# Hatch2021Badge0805_1.net
KiCad netlist of a schematic drawn in EAGLE
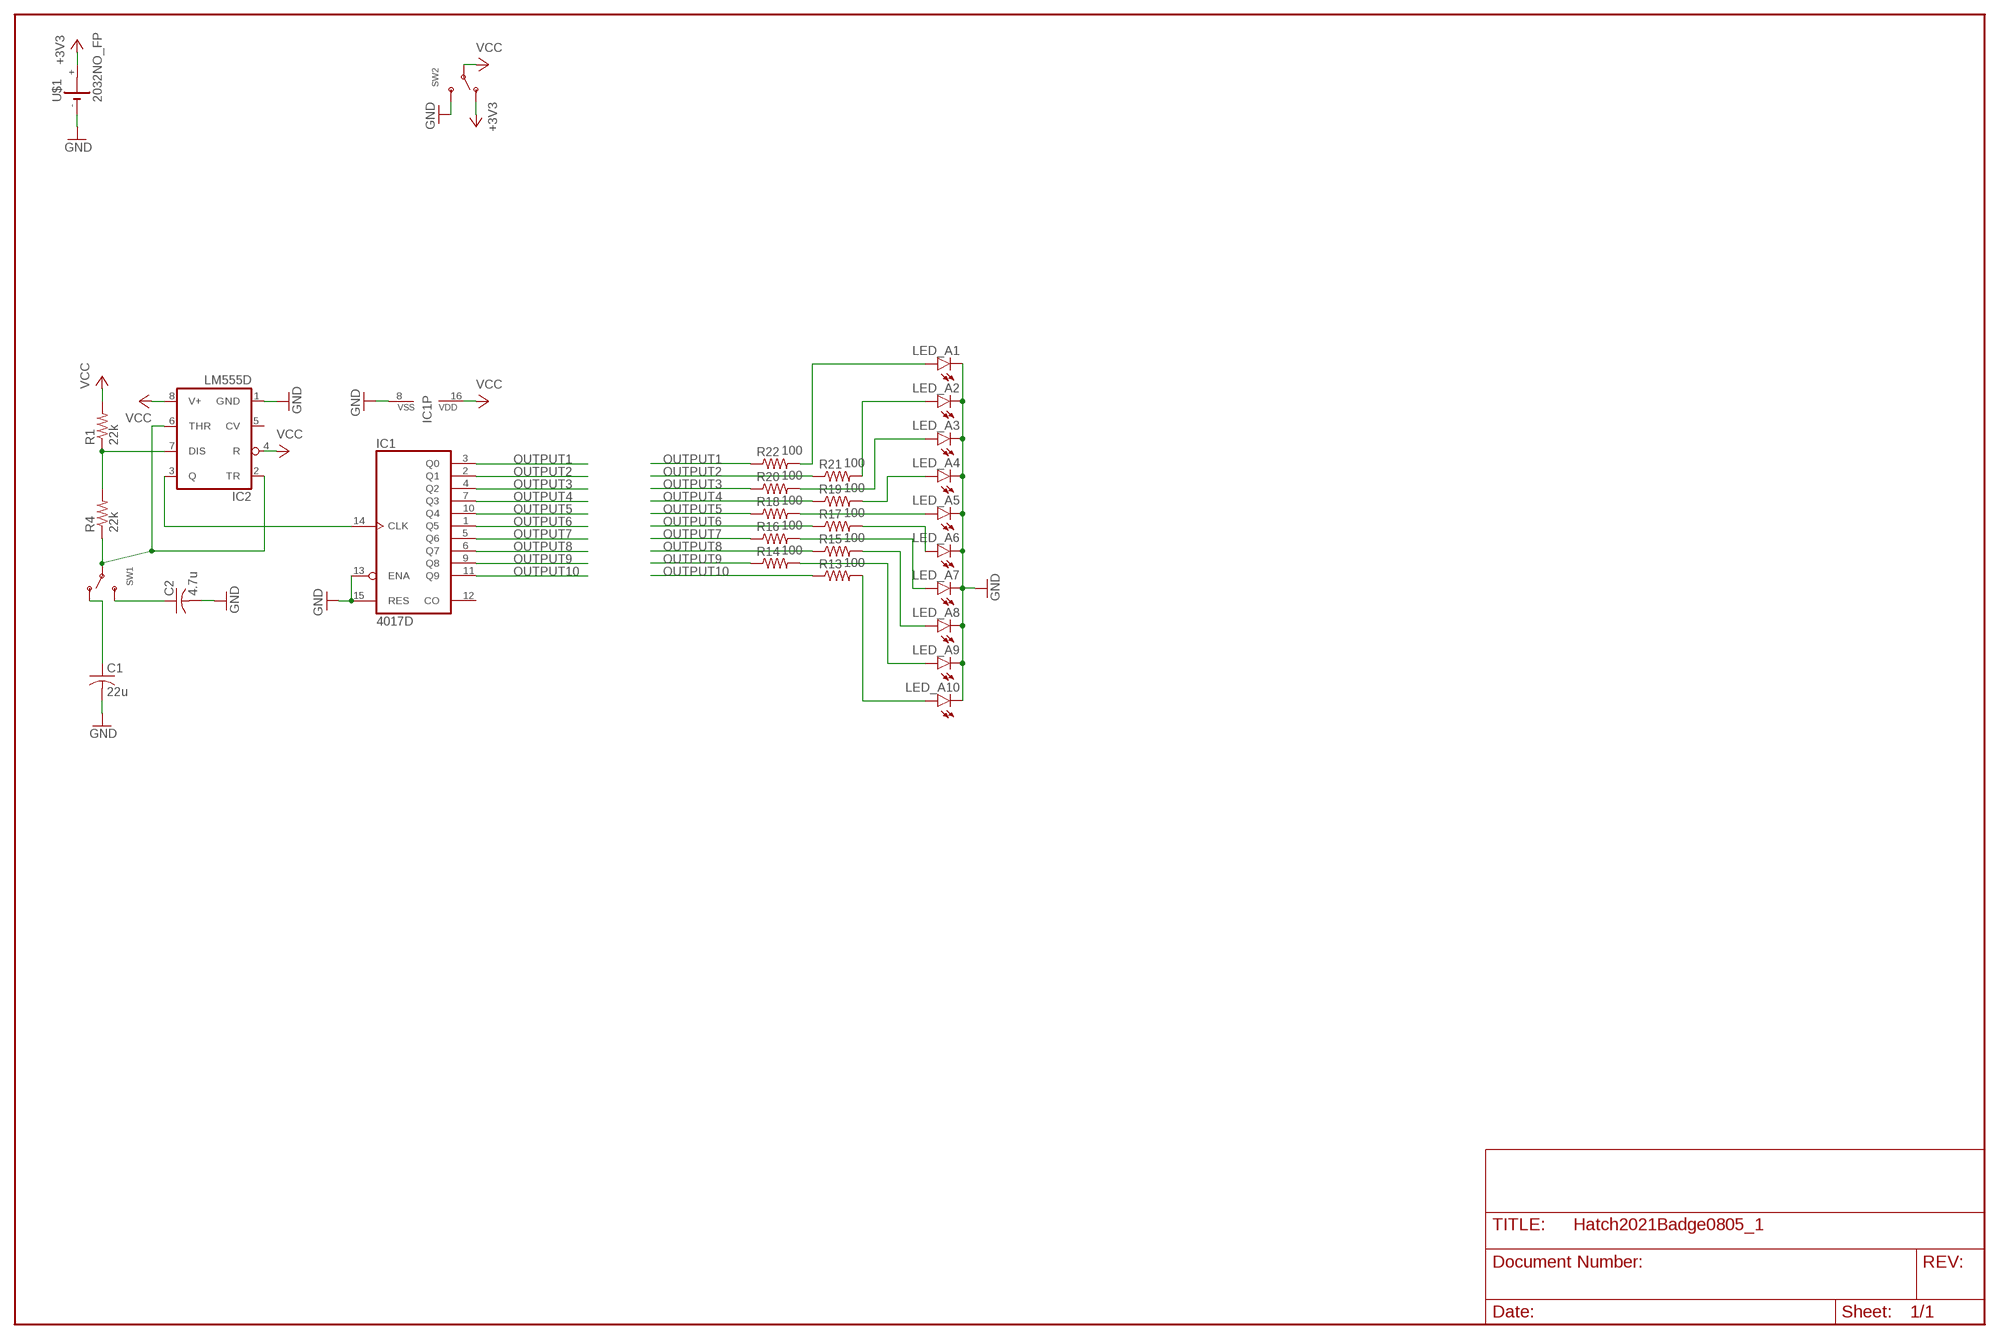
[diagram p0: schematic, sheet 1]

(export (version "E")
  (design (tool "Eeschema 10.0.6"))
  (components
    (comp (ref "C1")
      (value "22u")
      (footprint "eagle-import:C0805")
      (libsource (lib "eagle-import") (part "C-USC0805"))
    )
    (comp (ref "C2")
      (value "4.7u")
      (footprint "eagle-import:C0805")
      (libsource (lib "eagle-import") (part "C-USC0805"))
    )
    (comp (ref "IC1")
      (value "4017D")
      (footprint "eagle-import:SO16")
      (libsource (lib "eagle-import") (part "4017D"))
    )
    (comp (ref "IC2")
      (value "LM555D")
      (footprint "eagle-import:SO08")
      (libsource (lib "eagle-import") (part "555DLM"))
    )
    (comp (ref "LED_A1")
      (value "LEDSML0805")
      (footprint "eagle-import:SML0805")
      (libsource (lib "eagle-import") (part "LEDSML0805"))
    )
    (comp (ref "LED_A2")
      (value "LEDSML0805")
      (footprint "eagle-import:SML0805")
      (libsource (lib "eagle-import") (part "LEDSML0805"))
    )
    (comp (ref "LED_A3")
      (value "LEDSML0805")
      (footprint "eagle-import:SML0805")
      (libsource (lib "eagle-import") (part "LEDSML0805"))
    )
    (comp (ref "LED_A4")
      (value "LEDSML0805")
      (footprint "eagle-import:SML0805")
      (libsource (lib "eagle-import") (part "LEDSML0805"))
    )
    (comp (ref "LED_A5")
      (value "LEDSML0805")
      (footprint "eagle-import:SML0805")
      (libsource (lib "eagle-import") (part "LEDSML0805"))
    )
    (comp (ref "LED_A6")
      (value "LEDSML0805")
      (footprint "eagle-import:SML0805")
      (libsource (lib "eagle-import") (part "LEDSML0805"))
    )
    (comp (ref "LED_A7")
      (value "LEDSML0805")
      (footprint "eagle-import:SML0805")
      (libsource (lib "eagle-import") (part "LEDSML0805"))
    )
    (comp (ref "LED_A8")
      (value "LEDSML0805")
      (footprint "eagle-import:SML0805")
      (libsource (lib "eagle-import") (part "LEDSML0805"))
    )
    (comp (ref "LED_A9")
      (value "LEDSML0805")
      (footprint "eagle-import:SML0805")
      (libsource (lib "eagle-import") (part "LEDSML0805"))
    )
    (comp (ref "LED_A10")
      (value "LEDSML0805")
      (footprint "eagle-import:SML0805")
      (libsource (lib "eagle-import") (part "LEDSML0805"))
    )
    (comp (ref "R1")
      (value "22k")
      (footprint "eagle-import:R0805")
      (libsource (lib "eagle-import") (part "R-US_R0805"))
    )
    (comp (ref "R4")
      (value "22k")
      (footprint "eagle-import:R0805")
      (libsource (lib "eagle-import") (part "R-US_R0805"))
    )
    (comp (ref "R13")
      (value "100")
      (footprint "eagle-import:R0805")
      (libsource (lib "eagle-import") (part "R-US_R0805"))
    )
    (comp (ref "R14")
      (value "100")
      (footprint "eagle-import:R0805")
      (libsource (lib "eagle-import") (part "R-US_R0805"))
    )
    (comp (ref "R15")
      (value "100")
      (footprint "eagle-import:R0805")
      (libsource (lib "eagle-import") (part "R-US_R0805"))
    )
    (comp (ref "R16")
      (value "100")
      (footprint "eagle-import:R0805")
      (libsource (lib "eagle-import") (part "R-US_R0805"))
    )
    (comp (ref "R17")
      (value "100")
      (footprint "eagle-import:R0805")
      (libsource (lib "eagle-import") (part "R-US_R0805"))
    )
    (comp (ref "R18")
      (value "100")
      (footprint "eagle-import:R0805")
      (libsource (lib "eagle-import") (part "R-US_R0805"))
    )
    (comp (ref "R19")
      (value "100")
      (footprint "eagle-import:R0805")
      (libsource (lib "eagle-import") (part "R-US_R0805"))
    )
    (comp (ref "R20")
      (value "100")
      (footprint "eagle-import:R0805")
      (libsource (lib "eagle-import") (part "R-US_R0805"))
    )
    (comp (ref "R21")
      (value "100")
      (footprint "eagle-import:R0805")
      (libsource (lib "eagle-import") (part "R-US_R0805"))
    )
    (comp (ref "R22")
      (value "100")
      (footprint "eagle-import:R0805")
      (libsource (lib "eagle-import") (part "R-US_R0805"))
    )
    (comp (ref "SW1")
      (value "SWITCH_SPDT")
      (footprint "eagle-import:SPDT_SMT_SSSS811101")
      (libsource (lib "eagle-import") (part "SWITCH_SPDT"))
    )
    (comp (ref "SW2")
      (value "SWITCH_SPDT")
      (footprint "eagle-import:SPDT_SMT_SSSS811101")
      (libsource (lib "eagle-import") (part "SWITCH_SPDT"))
    )
    (comp (ref "U$1")
      (value "2032NO_FP")
      (footprint "eagle-import:2032_NO_FP")
      (libsource (lib "eagle-import") (part "2032NO_FP"))
    )
  )
  (nets
    (net (code "1") (name "+3V3") (class "Default")
      (node (ref "SW2") (pin "A") (pinfunction "O_A") (pintype "passive"))
      (node (ref "U$1") (pin "+") (pinfunction "+_+") (pintype "passive"))
    )
    (net (code "2") (name "/OUTPUT1") (class "Default")
      (node (ref "IC1") (pin "3") (pinfunction "Q0_3") (pintype "output"))
      (node (ref "R22") (pin "1") (pinfunction "1_1") (pintype "passive"))
    )
    (net (code "3") (name "/OUTPUT2") (class "Default")
      (node (ref "IC1") (pin "2") (pinfunction "Q1_2") (pintype "output"))
      (node (ref "R21") (pin "1") (pinfunction "1_1") (pintype "passive"))
    )
    (net (code "4") (name "/OUTPUT3") (class "Default")
      (node (ref "IC1") (pin "4") (pinfunction "Q2_4") (pintype "output"))
      (node (ref "R20") (pin "1") (pinfunction "1_1") (pintype "passive"))
    )
    (net (code "5") (name "/OUTPUT4") (class "Default")
      (node (ref "IC1") (pin "7") (pinfunction "Q3_7") (pintype "output"))
      (node (ref "R19") (pin "1") (pinfunction "1_1") (pintype "passive"))
    )
    (net (code "6") (name "/OUTPUT5") (class "Default")
      (node (ref "IC1") (pin "10") (pinfunction "Q4_10") (pintype "output"))
      (node (ref "R18") (pin "1") (pinfunction "1_1") (pintype "passive"))
    )
    (net (code "7") (name "/OUTPUT6") (class "Default")
      (node (ref "IC1") (pin "1") (pinfunction "Q5_1") (pintype "output"))
      (node (ref "R17") (pin "1") (pinfunction "1_1") (pintype "passive"))
    )
    (net (code "8") (name "/OUTPUT7") (class "Default")
      (node (ref "IC1") (pin "5") (pinfunction "Q6_5") (pintype "output"))
      (node (ref "R16") (pin "1") (pinfunction "1_1") (pintype "passive"))
    )
    (net (code "9") (name "/OUTPUT8") (class "Default")
      (node (ref "IC1") (pin "6") (pinfunction "Q7_6") (pintype "output"))
      (node (ref "R15") (pin "1") (pinfunction "1_1") (pintype "passive"))
    )
    (net (code "10") (name "/OUTPUT9") (class "Default")
      (node (ref "IC1") (pin "9") (pinfunction "Q8_9") (pintype "output"))
      (node (ref "R14") (pin "1") (pinfunction "1_1") (pintype "passive"))
    )
    (net (code "11") (name "/OUTPUT10") (class "Default")
      (node (ref "IC1") (pin "11") (pinfunction "Q9_11") (pintype "output"))
      (node (ref "R13") (pin "1") (pinfunction "1_1") (pintype "passive"))
    )
    (net (code "12") (name "GND") (class "Default")
      (node (ref "C1") (pin "2") (pinfunction "2_2") (pintype "passive"))
      (node (ref "C2") (pin "2") (pinfunction "2_2") (pintype "passive"))
      (node (ref "IC1") (pin "13") (pinfunction "ENA_13") (pintype "input"))
      (node (ref "IC1") (pin "15") (pinfunction "RES_15") (pintype "input"))
      (node (ref "IC1") (pin "8") (pinfunction "VSS_8") (pintype "power_in"))
      (node (ref "IC2") (pin "1") (pinfunction "GND_1") (pintype "power_in"))
      (node (ref "LED_A1") (pin "C") (pinfunction "C_C") (pintype "passive"))
      (node (ref "LED_A10") (pin "C") (pinfunction "C_C") (pintype "passive"))
      (node (ref "LED_A2") (pin "C") (pinfunction "C_C") (pintype "passive"))
      (node (ref "LED_A3") (pin "C") (pinfunction "C_C") (pintype "passive"))
      (node (ref "LED_A4") (pin "C") (pinfunction "C_C") (pintype "passive"))
      (node (ref "LED_A5") (pin "C") (pinfunction "C_C") (pintype "passive"))
      (node (ref "LED_A6") (pin "C") (pinfunction "C_C") (pintype "passive"))
      (node (ref "LED_A7") (pin "C") (pinfunction "C_C") (pintype "passive"))
      (node (ref "LED_A8") (pin "C") (pinfunction "C_C") (pintype "passive"))
      (node (ref "LED_A9") (pin "C") (pinfunction "C_C") (pintype "passive"))
      (node (ref "SW2") (pin "C") (pinfunction "S_C") (pintype "passive"))
      (node (ref "U$1") (pin "-") (pinfunction "-_-") (pintype "passive"))
    )
    (net (code "13") (name "Net-(IC1A-CLK)") (class "Default")
      (node (ref "IC1") (pin "14") (pinfunction "CLK_14") (pintype "input"))
      (node (ref "IC2") (pin "3") (pinfunction "Q_3") (pintype "output"))
    )
    (net (code "14") (name "Net-(IC2-DIS)") (class "Default")
      (node (ref "IC2") (pin "7") (pinfunction "DIS_7") (pintype "input"))
      (node (ref "R1") (pin "1") (pinfunction "1_1") (pintype "passive"))
      (node (ref "R4") (pin "2") (pinfunction "2_2") (pintype "passive"))
    )
    (net (code "15") (name "Net-(IC2-THR)") (class "Default")
      (node (ref "IC2") (pin "2") (pinfunction "TR_2") (pintype "input"))
      (node (ref "IC2") (pin "6") (pinfunction "THR_6") (pintype "input"))
      (node (ref "R4") (pin "1") (pinfunction "1_1") (pintype "passive"))
      (node (ref "SW1") (pin "B") (pinfunction "P_B") (pintype "passive"))
    )
    (net (code "16") (name "Net-(LED_A1-PadA)") (class "Default")
      (node (ref "LED_A1") (pin "A") (pinfunction "A_A") (pintype "passive"))
      (node (ref "R22") (pin "2") (pinfunction "2_2") (pintype "passive"))
    )
    (net (code "17") (name "Net-(LED_A2-PadA)") (class "Default")
      (node (ref "LED_A2") (pin "A") (pinfunction "A_A") (pintype "passive"))
      (node (ref "R21") (pin "2") (pinfunction "2_2") (pintype "passive"))
    )
    (net (code "18") (name "Net-(LED_A3-PadA)") (class "Default")
      (node (ref "LED_A3") (pin "A") (pinfunction "A_A") (pintype "passive"))
      (node (ref "R20") (pin "2") (pinfunction "2_2") (pintype "passive"))
    )
    (net (code "19") (name "Net-(LED_A4-PadA)") (class "Default")
      (node (ref "LED_A4") (pin "A") (pinfunction "A_A") (pintype "passive"))
      (node (ref "R19") (pin "2") (pinfunction "2_2") (pintype "passive"))
    )
    (net (code "20") (name "Net-(LED_A5-PadA)") (class "Default")
      (node (ref "LED_A5") (pin "A") (pinfunction "A_A") (pintype "passive"))
      (node (ref "R18") (pin "2") (pinfunction "2_2") (pintype "passive"))
    )
    (net (code "21") (name "Net-(LED_A6-PadA)") (class "Default")
      (node (ref "LED_A6") (pin "A") (pinfunction "A_A") (pintype "passive"))
      (node (ref "R17") (pin "2") (pinfunction "2_2") (pintype "passive"))
    )
    (net (code "22") (name "Net-(LED_A7-PadA)") (class "Default")
      (node (ref "LED_A7") (pin "A") (pinfunction "A_A") (pintype "passive"))
      (node (ref "R16") (pin "2") (pinfunction "2_2") (pintype "passive"))
    )
    (net (code "23") (name "Net-(LED_A8-PadA)") (class "Default")
      (node (ref "LED_A8") (pin "A") (pinfunction "A_A") (pintype "passive"))
      (node (ref "R15") (pin "2") (pinfunction "2_2") (pintype "passive"))
    )
    (net (code "24") (name "Net-(LED_A9-PadA)") (class "Default")
      (node (ref "LED_A9") (pin "A") (pinfunction "A_A") (pintype "passive"))
      (node (ref "R14") (pin "2") (pinfunction "2_2") (pintype "passive"))
    )
    (net (code "25") (name "Net-(LED_A10-PadA)") (class "Default")
      (node (ref "LED_A10") (pin "A") (pinfunction "A_A") (pintype "passive"))
      (node (ref "R13") (pin "2") (pinfunction "2_2") (pintype "passive"))
    )
    (net (code "26") (name "Net-(SW1-O)") (class "Default")
      (node (ref "C1") (pin "1") (pinfunction "1_1") (pintype "passive"))
      (node (ref "SW1") (pin "A") (pinfunction "O_A") (pintype "passive"))
    )
    (net (code "27") (name "Net-(SW1-S)") (class "Default")
      (node (ref "C2") (pin "1") (pinfunction "1_1") (pintype "passive"))
      (node (ref "SW1") (pin "C") (pinfunction "S_C") (pintype "passive"))
    )
    (net (code "28") (name "VCC") (class "Default")
      (node (ref "IC1") (pin "16") (pinfunction "VDD_16") (pintype "power_in"))
      (node (ref "IC2") (pin "4") (pinfunction "R_4") (pintype "input"))
      (node (ref "IC2") (pin "8") (pinfunction "V+_8") (pintype "power_in"))
      (node (ref "R1") (pin "2") (pinfunction "2_2") (pintype "passive"))
      (node (ref "SW2") (pin "B") (pinfunction "P_B") (pintype "passive"))
    )
    (net (code "29") (name "unconnected-(IC1A-CO-Pad12)") (class "Default")
      (node (ref "IC1") (pin "12") (pinfunction "CO_12") (pintype "output"))
    )
    (net (code "30") (name "unconnected-(IC2-CV-Pad5)") (class "Default")
      (node (ref "IC2") (pin "5") (pinfunction "CV_5") (pintype "input"))
    )
  )
)
